# profboard.net
KiCad netlist of a schematic drawn in EAGLE
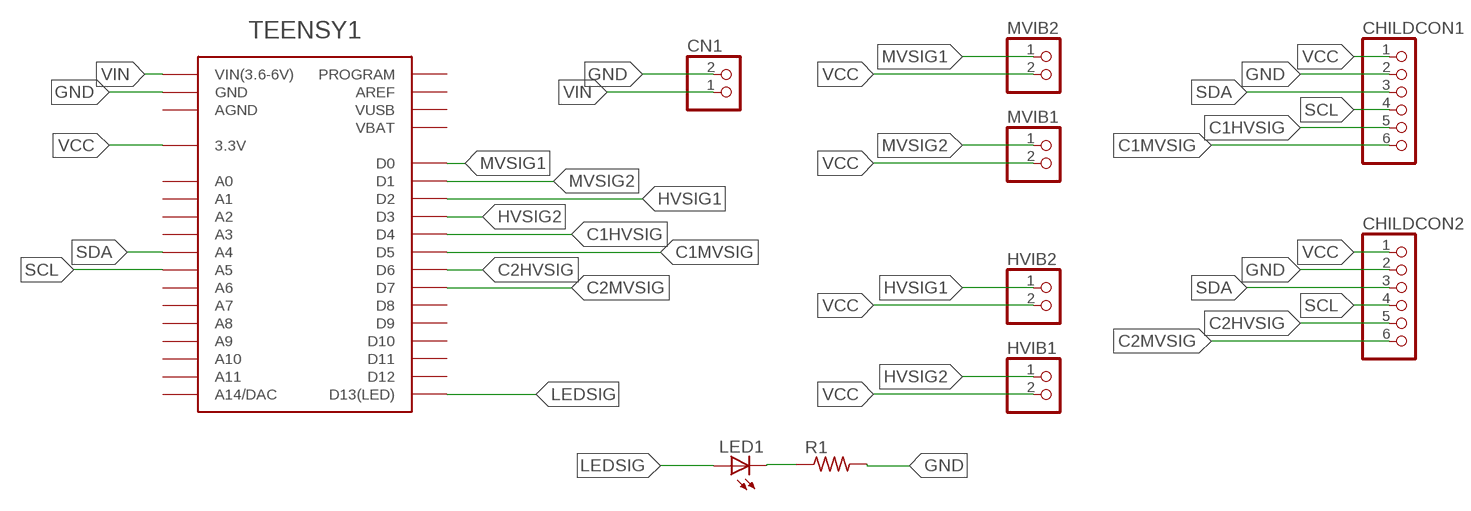
[diagram p0: schematic, sheet 1]

(export (version "E")
  (design (tool "Eeschema 10.0.6"))
  (components
    (comp (ref "CHILDCON1")
      (value "PINHD-1X6")
      (footprint "eagle-import:1X06")
      (libsource (lib "eagle-import") (part "PINHD-1X6"))
    )
    (comp (ref "CHILDCON2")
      (value "PINHD-1X6")
      (footprint "eagle-import:1X06")
      (libsource (lib "eagle-import") (part "PINHD-1X6"))
    )
    (comp (ref "CN1")
      (value "JST_2PIN-THM-RA")
      (footprint "eagle-import:JST-PH-2-THM-RA")
      (libsource (lib "eagle-import") (part "JST_2PIN-THM-RA"))
    )
    (comp (ref "HVIB1")
      (value "PINHD-1X2")
      (footprint "eagle-import:1X02")
      (libsource (lib "eagle-import") (part "PINHD-1X2"))
    )
    (comp (ref "HVIB2")
      (value "PINHD-1X2")
      (footprint "eagle-import:1X02")
      (libsource (lib "eagle-import") (part "PINHD-1X2"))
    )
    (comp (ref "LED1")
      (value "LED5MM")
      (footprint "eagle-import:LED5MM")
      (libsource (lib "eagle-import") (part "LED5MM"))
    )
    (comp (ref "MVIB1")
      (value "PINHD-1X2")
      (footprint "eagle-import:1X02")
      (libsource (lib "eagle-import") (part "PINHD-1X2"))
    )
    (comp (ref "MVIB2")
      (value "PINHD-1X2")
      (footprint "eagle-import:1X02")
      (libsource (lib "eagle-import") (part "PINHD-1X2"))
    )
    (comp (ref "R1")
      (value "R-US_0204/7")
      (footprint "eagle-import:0204_7")
      (libsource (lib "eagle-import") (part "R-US_0204/7"))
    )
    (comp (ref "TEENSY1")
      (value "TEENSY3.2")
      (footprint "eagle-import:TEENSY3.2")
      (libsource (lib "eagle-import") (part "TEENSY3.2"))
    )
  )
  (nets
    (net (code "1") (name "C1HVSIG") (class "Default")
      (node (ref "CHILDCON1") (pin "5") (pinfunction "5_5") (pintype "passive"))
      (node (ref "TEENSY1") (pin "4") (pinfunction "D4_4") (pintype "bidirectional"))
    )
    (net (code "2") (name "C1MVSIG") (class "Default")
      (node (ref "CHILDCON1") (pin "6") (pinfunction "6_6") (pintype "passive"))
      (node (ref "TEENSY1") (pin "5") (pinfunction "D5_5") (pintype "bidirectional"))
    )
    (net (code "3") (name "C2HVSIG") (class "Default")
      (node (ref "CHILDCON2") (pin "5") (pinfunction "5_5") (pintype "passive"))
      (node (ref "TEENSY1") (pin "6") (pinfunction "D6_6") (pintype "bidirectional"))
    )
    (net (code "4") (name "C2MVSIG") (class "Default")
      (node (ref "CHILDCON2") (pin "6") (pinfunction "6_6") (pintype "passive"))
      (node (ref "TEENSY1") (pin "7") (pinfunction "D7_7") (pintype "bidirectional"))
    )
    (net (code "5") (name "GND") (class "Default")
      (node (ref "CHILDCON1") (pin "2") (pinfunction "2_2") (pintype "passive"))
      (node (ref "CHILDCON2") (pin "2") (pinfunction "2_2") (pintype "passive"))
      (node (ref "CN1") (pin "2") (pinfunction "1_2") (pintype "passive"))
      (node (ref "R1") (pin "2") (pinfunction "2_2") (pintype "passive"))
      (node (ref "TEENSY1") (pin "G") (pinfunction "GND_G") (pintype "bidirectional"))
      (node (ref "TEENSY1") (pin "GND") (pinfunction "GND_GND") (pintype "bidirectional"))
    )
    (net (code "6") (name "HVSIG1") (class "Default")
      (node (ref "HVIB2") (pin "1") (pinfunction "1_1") (pintype "passive"))
      (node (ref "TEENSY1") (pin "2") (pinfunction "D2_2") (pintype "bidirectional"))
    )
    (net (code "7") (name "HVSIG2") (class "Default")
      (node (ref "HVIB1") (pin "1") (pinfunction "1_1") (pintype "passive"))
      (node (ref "TEENSY1") (pin "3") (pinfunction "D3_3") (pintype "bidirectional"))
    )
    (net (code "8") (name "LEDSIG") (class "Default")
      (node (ref "LED1") (pin "A") (pinfunction "A_A") (pintype "passive"))
      (node (ref "TEENSY1") (pin "13") (pinfunction "D13(LED)_13") (pintype "bidirectional"))
    )
    (net (code "9") (name "MVSIG1") (class "Default")
      (node (ref "MVIB2") (pin "1") (pinfunction "1_1") (pintype "passive"))
      (node (ref "TEENSY1") (pin "0") (pinfunction "D0_0") (pintype "bidirectional"))
    )
    (net (code "10") (name "MVSIG2") (class "Default")
      (node (ref "MVIB1") (pin "1") (pinfunction "1_1") (pintype "passive"))
      (node (ref "TEENSY1") (pin "1") (pinfunction "D1_1") (pintype "bidirectional"))
    )
    (net (code "11") (name "Net-(LED1-C)") (class "Default")
      (node (ref "LED1") (pin "K") (pinfunction "C_K") (pintype "passive"))
      (node (ref "R1") (pin "1") (pinfunction "1_1") (pintype "passive"))
    )
    (net (code "12") (name "SCL") (class "Default")
      (node (ref "CHILDCON1") (pin "4") (pinfunction "4_4") (pintype "passive"))
      (node (ref "CHILDCON2") (pin "4") (pinfunction "4_4") (pintype "passive"))
      (node (ref "TEENSY1") (pin "19") (pinfunction "A5_19") (pintype "bidirectional"))
    )
    (net (code "13") (name "SDA") (class "Default")
      (node (ref "CHILDCON1") (pin "3") (pinfunction "3_3") (pintype "passive"))
      (node (ref "CHILDCON2") (pin "3") (pinfunction "3_3") (pintype "passive"))
      (node (ref "TEENSY1") (pin "18") (pinfunction "A4_18") (pintype "bidirectional"))
    )
    (net (code "14") (name "VCC") (class "Default")
      (node (ref "CHILDCON1") (pin "1") (pinfunction "1_1") (pintype "passive"))
      (node (ref "CHILDCON2") (pin "1") (pinfunction "1_1") (pintype "passive"))
      (node (ref "HVIB1") (pin "2") (pinfunction "2_2") (pintype "passive"))
      (node (ref "HVIB2") (pin "2") (pinfunction "2_2") (pintype "passive"))
      (node (ref "MVIB1") (pin "2") (pinfunction "2_2") (pintype "passive"))
      (node (ref "MVIB2") (pin "2") (pinfunction "2_2") (pintype "passive"))
      (node (ref "TEENSY1") (pin "3V") (pinfunction "3.3V_3V") (pintype "bidirectional"))
      (node (ref "TEENSY1") (pin "V") (pinfunction "3.3V_V") (pintype "bidirectional"))
    )
    (net (code "15") (name "VIN") (class "Default")
      (node (ref "CN1") (pin "1") (pinfunction "2_1") (pintype "passive"))
      (node (ref "TEENSY1") (pin "VIN") (pinfunction "VIN(3.6-6V)_VIN") (pintype "bidirectional"))
    )
    (net (code "16") (name "unconnected-(TEENSY1-A0-Pad14)") (class "Default")
      (node (ref "TEENSY1") (pin "14") (pinfunction "A0_14") (pintype "bidirectional"))
    )
    (net (code "17") (name "unconnected-(TEENSY1-A1-Pad15)") (class "Default")
      (node (ref "TEENSY1") (pin "15") (pinfunction "A1_15") (pintype "bidirectional"))
    )
    (net (code "18") (name "unconnected-(TEENSY1-A2-Pad16)") (class "Default")
      (node (ref "TEENSY1") (pin "16") (pinfunction "A2_16") (pintype "bidirectional"))
    )
    (net (code "19") (name "unconnected-(TEENSY1-A3-Pad17)") (class "Default")
      (node (ref "TEENSY1") (pin "17") (pinfunction "A3_17") (pintype "bidirectional"))
    )
    (net (code "20") (name "unconnected-(TEENSY1-A6-Pad20)") (class "Default")
      (node (ref "TEENSY1") (pin "20") (pinfunction "A6_20") (pintype "bidirectional"))
    )
    (net (code "21") (name "unconnected-(TEENSY1-A7-Pad21)") (class "Default")
      (node (ref "TEENSY1") (pin "21") (pinfunction "A7_21") (pintype "bidirectional"))
    )
    (net (code "22") (name "unconnected-(TEENSY1-A8-Pad22)") (class "Default")
      (node (ref "TEENSY1") (pin "22") (pinfunction "A8_22") (pintype "bidirectional"))
    )
    (net (code "23") (name "unconnected-(TEENSY1-A9-Pad23)") (class "Default")
      (node (ref "TEENSY1") (pin "23") (pinfunction "A9_23") (pintype "bidirectional"))
    )
    (net (code "24") (name "unconnected-(TEENSY1-A14{slash}DAC-PadD)") (class "Default")
      (node (ref "TEENSY1") (pin "D") (pinfunction "A14/DAC_D") (pintype "bidirectional"))
    )
    (net (code "25") (name "unconnected-(TEENSY1-D8-Pad8)") (class "Default")
      (node (ref "TEENSY1") (pin "8") (pinfunction "D8_8") (pintype "bidirectional"))
    )
    (net (code "26") (name "unconnected-(TEENSY1-D9-Pad9)") (class "Default")
      (node (ref "TEENSY1") (pin "9") (pinfunction "D9_9") (pintype "bidirectional"))
    )
    (net (code "27") (name "unconnected-(TEENSY1-D10-Pad10)") (class "Default")
      (node (ref "TEENSY1") (pin "10") (pinfunction "D10_10") (pintype "bidirectional"))
    )
    (net (code "28") (name "unconnected-(TEENSY1-D11-Pad11)") (class "Default")
      (node (ref "TEENSY1") (pin "11") (pinfunction "D11_11") (pintype "bidirectional"))
    )
    (net (code "29") (name "unconnected-(TEENSY1-D12-Pad12)") (class "Default")
      (node (ref "TEENSY1") (pin "12") (pinfunction "D12_12") (pintype "bidirectional"))
    )
    (net (code "30") (name "unconnected-(TEENSY1-PROGRAM-PadP)") (class "Default")
      (node (ref "TEENSY1") (pin "P") (pinfunction "PROGRAM_P") (pintype "bidirectional"))
    )
    (net (code "31") (name "unconnected-(TEENSY1-PadA10)") (class "Default")
      (node (ref "TEENSY1") (pin "A10") (pinfunction "A10_A10") (pintype "bidirectional"))
    )
    (net (code "32") (name "unconnected-(TEENSY1-PadA11)") (class "Default")
      (node (ref "TEENSY1") (pin "A11") (pinfunction "A11_A11") (pintype "bidirectional"))
    )
    (net (code "33") (name "unconnected-(TEENSY1-PadAGND)") (class "Default")
      (node (ref "TEENSY1") (pin "AGND") (pinfunction "AGND_AGND") (pintype "bidirectional"))
    )
    (net (code "34") (name "unconnected-(TEENSY1-PadAREF)") (class "Default")
      (node (ref "TEENSY1") (pin "AREF") (pinfunction "AREF_AREF") (pintype "bidirectional"))
    )
    (net (code "35") (name "unconnected-(TEENSY1-PadVUSB)") (class "Default")
      (node (ref "TEENSY1") (pin "VUSB") (pinfunction "VUSB_VUSB") (pintype "bidirectional"))
    )
    (net (code "36") (name "unconnected-(TEENSY1-VBAT-PadBAT)") (class "Default")
      (node (ref "TEENSY1") (pin "BAT") (pinfunction "VBAT_BAT") (pintype "bidirectional"))
    )
  )
)
